# BSPD_Simulation.net
KiCad netlist of a schematic drawn in Altium Designer
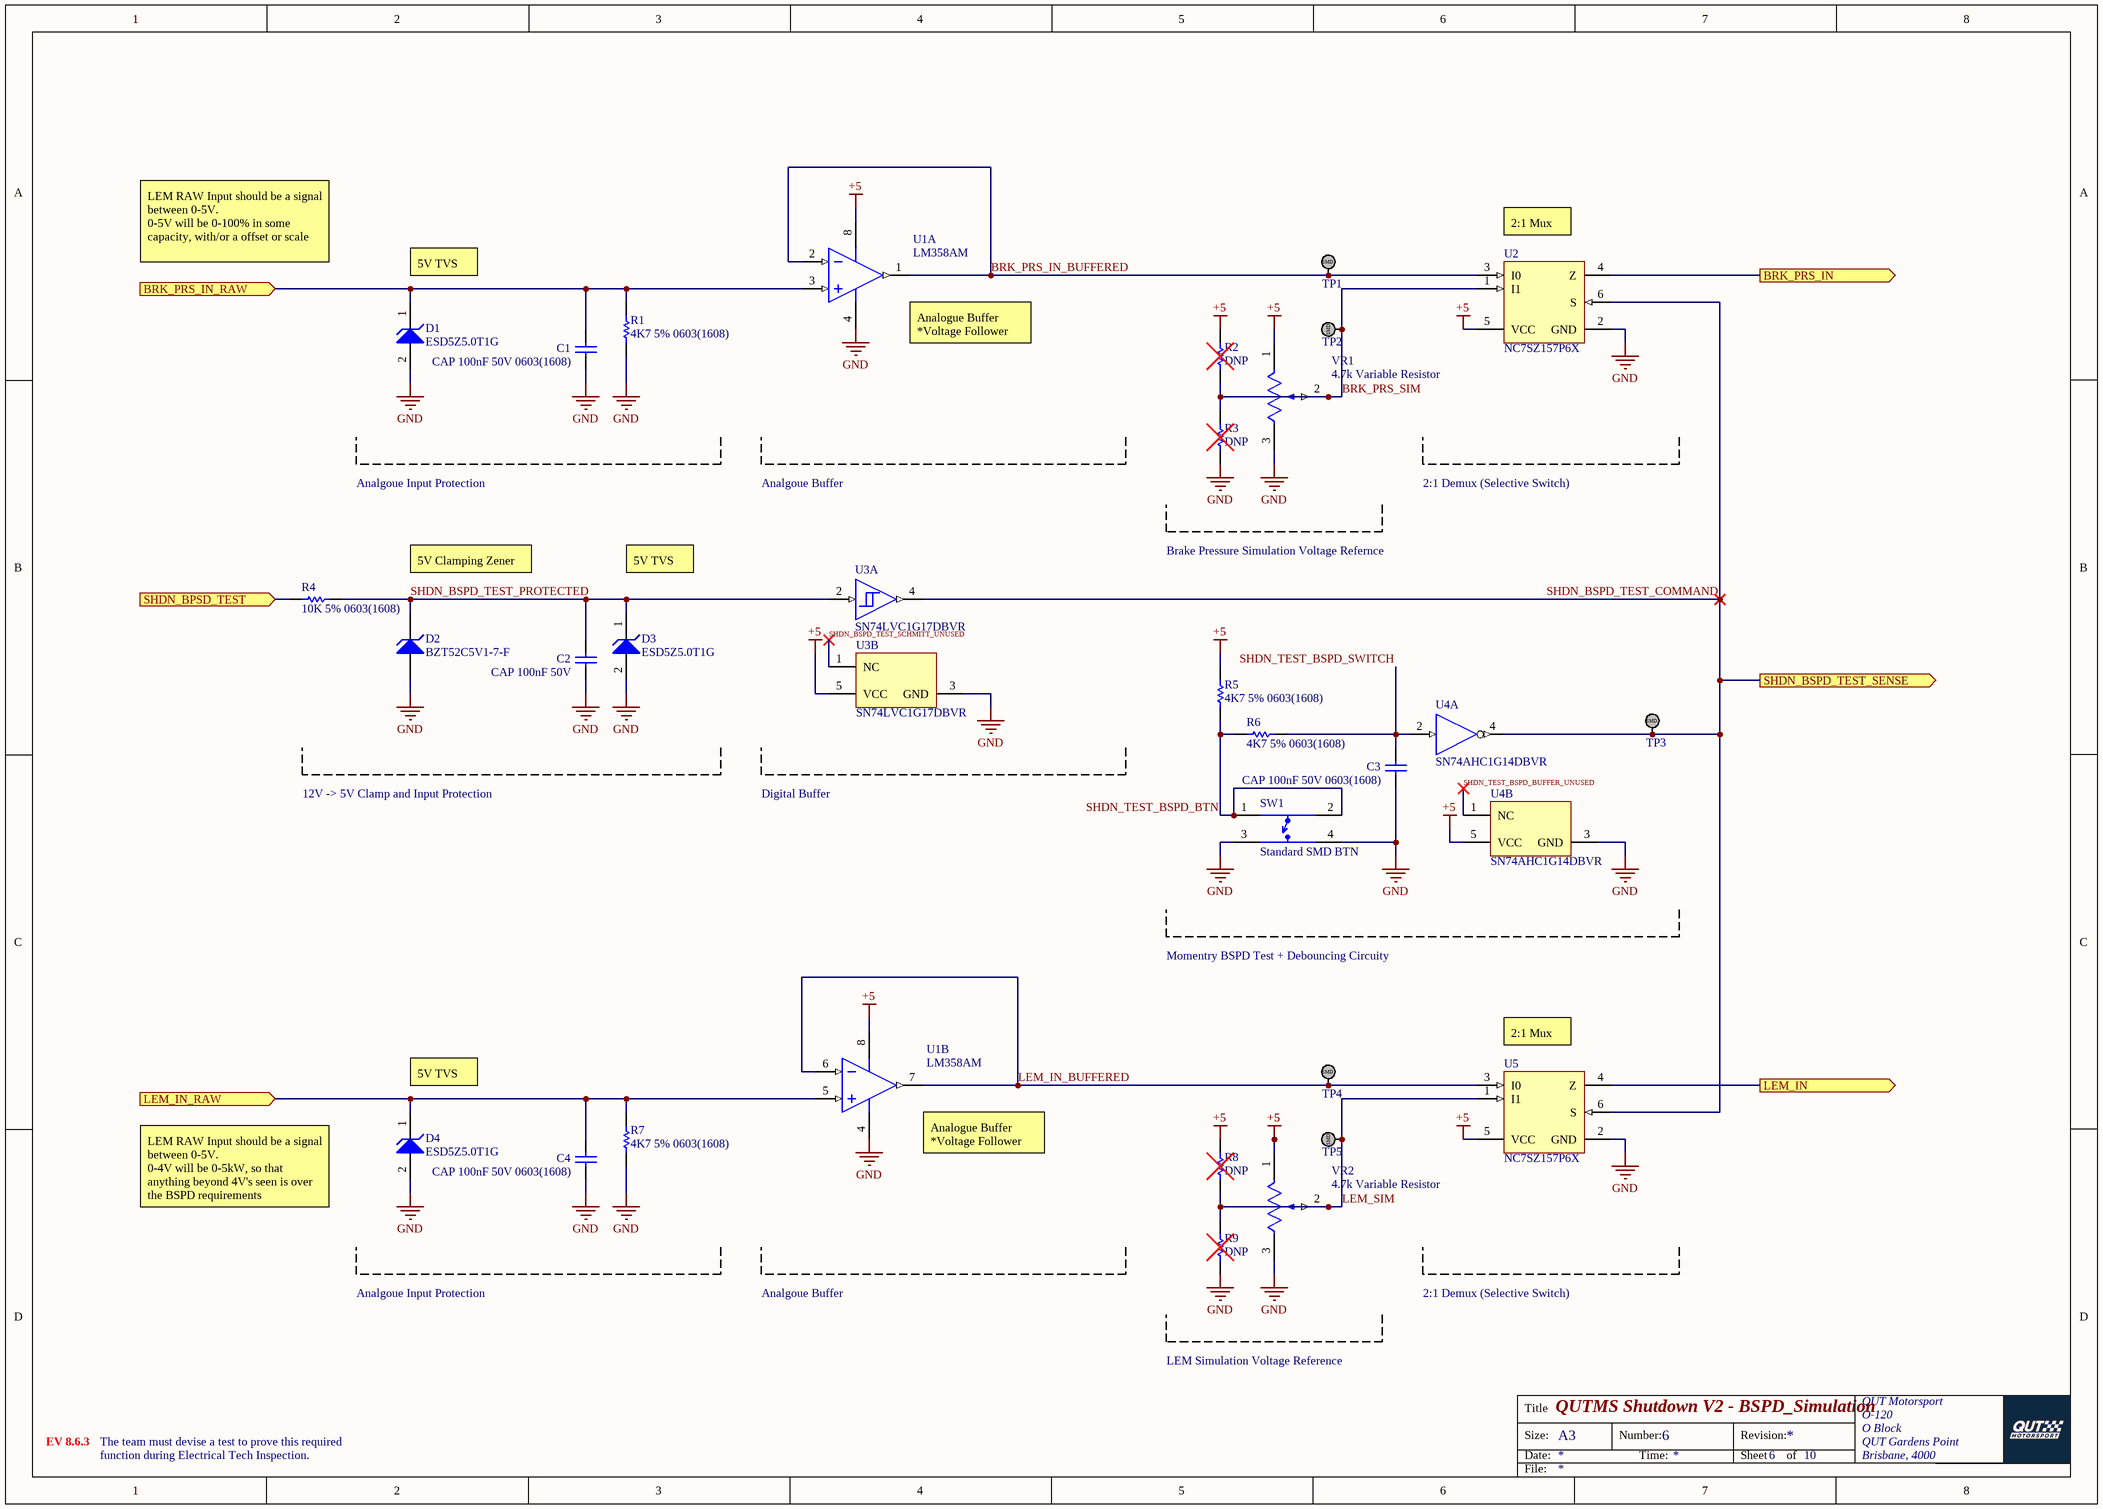
[diagram p0: BSPD_Simulation.SchDoc]

(export (version "E")
  (design (tool "Eeschema 10.0.6"))
  (components
    (comp (ref "C1")
      (value "CAP 100nF 50V 0603(1608)")
      (footprint "CAPC0603(1608)100_L")
      (description "CAP 100nF 50V ±5% 0603 (1608 Metric) Thickness 1mm SMD")
      (fields (field (name "TOLERANCE") "Â±5%"))
      (libsource (lib "Altium Content Vault") (part "CAP"))
    )
    (comp (ref "C2")
      (value "CAP 100nF 50V")
      (footprint "CAPC0603(1608)100_L")
      (description "CAP 100nF 50V ±5% 0603 (1608 Metric) Thickness 1mm SMD")
      (fields (field (name "TOLERANCE") "Â±5%"))
      (libsource (lib "Altium Content Vault") (part "CAP"))
    )
    (comp (ref "C3")
      (value "CAP 100nF 50V 0603(1608)")
      (footprint "CAPC0603(1608)100_L")
      (description "CAP 100nF 50V ±5% 0603 (1608 Metric) Thickness 1mm SMD")
      (fields (field (name "TOLERANCE") "Â±5%"))
      (libsource (lib "Altium Content Vault") (part "CAP"))
    )
    (comp (ref "C4")
      (value "CAP 100nF 50V 0603(1608)")
      (footprint "CAPC0603(1608)100_L")
      (description "CAP 100nF 50V ±5% 0603 (1608 Metric) Thickness 1mm SMD")
      (fields (field (name "TOLERANCE") "Â±5%"))
      (libsource (lib "Altium Content Vault") (part "CAP"))
    )
    (comp (ref "D1")
      (value "ESD5Z5.0T1G")
      (footprint "ONSC-SOD-523-2-502-01_V")
      (fields (field (name "MANUFACTURER") "On Semiconductor"))
      (libsource (lib "Altium Content Vault") (part "ONSC-K1A2-2"))
    )
    (comp (ref "D2")
      (value "BZT52C5V1-7-F")
      (footprint "DIOD-SOD123_V")
      (description "Surface Mount Zener Diode, 5.1 V, -65 to 150 degC, 2-Pin SMD (SOD-123), RoHS, Tape and Reel")
      (fields (field (name "MANUFACTURER") "DiodesIncorporated"))
      (libsource (lib "Altium Content Vault") (part "DZEN-AK-2"))
    )
    (comp (ref "D3")
      (value "ESD5Z5.0T1G")
      (footprint "ONSC-SOD-523-2-502-01_V")
      (fields (field (name "MANUFACTURER") "On Semiconductor"))
      (libsource (lib "Altium Content Vault") (part "ONSC-K1A2-2"))
    )
    (comp (ref "D4")
      (value "ESD5Z5.0T1G")
      (footprint "ONSC-SOD-523-2-502-01_V")
      (fields (field (name "MANUFACTURER") "On Semiconductor"))
      (libsource (lib "Altium Content Vault") (part "ONSC-K1A2-2"))
    )
    (comp (ref "R1")
      (value "4K7 5% 0603(1608)")
      (footprint "RESC0603(1608)_N")
      (description "4K7 0.1W 5% 0603 (1608 Metric)  SMD")
      (fields (field (name "TOLERANCE") "5 %") (field (name "POWER") "0.1 W"))
      (libsource (lib "Altium Content Vault") (part "RES"))
    )
    (comp (ref "R2")
      (value "DNP")
      (footprint "RESC0603(1608)_L")
      (description "0603 (1608 Metric) Chip Resistor")
      (libsource (lib "Altium Content Vault") (part "RES_3"))
    )
    (comp (ref "R3")
      (value "DNP")
      (footprint "RESC0603(1608)_L")
      (description "0603 (1608 Metric) Chip Resistor")
      (libsource (lib "Altium Content Vault") (part "RES_3"))
    )
    (comp (ref "R4")
      (value "10K 5% 0603(1608)")
      (footprint "RESC0603(1608)_N")
      (description "10K 0.1W 5% 0603 (1608 Metric)  SMD")
      (fields (field (name "TOLERANCE") "5 %") (field (name "POWER") "0.1 W"))
      (libsource (lib "Altium Content Vault") (part "RES"))
    )
    (comp (ref "R5")
      (value "4K7 5% 0603(1608)")
      (footprint "RESC0603(1608)_N")
      (description "4K7 0.1W 5% 0603 (1608 Metric)  SMD")
      (fields (field (name "TOLERANCE") "5 %") (field (name "POWER") "0.1 W"))
      (libsource (lib "Altium Content Vault") (part "RES"))
    )
    (comp (ref "R6")
      (value "4K7 5% 0603(1608)")
      (footprint "RESC0603(1608)_N")
      (description "4K7 0.1W 5% 0603 (1608 Metric)  SMD")
      (fields (field (name "TOLERANCE") "5 %") (field (name "POWER") "0.1 W"))
      (libsource (lib "Altium Content Vault") (part "RES"))
    )
    (comp (ref "R7")
      (value "4K7 5% 0603(1608)")
      (footprint "RESC0603(1608)_N")
      (description "4K7 0.1W 5% 0603 (1608 Metric)  SMD")
      (fields (field (name "TOLERANCE") "5 %") (field (name "POWER") "0.1 W"))
      (libsource (lib "Altium Content Vault") (part "RES"))
    )
    (comp (ref "R8")
      (value "DNP")
      (footprint "RESC0603(1608)_L")
      (description "0603 (1608 Metric) Chip Resistor")
      (libsource (lib "Altium Content Vault") (part "RES_3"))
    )
    (comp (ref "R9")
      (value "DNP")
      (footprint "RESC0603(1608)_L")
      (description "0603 (1608 Metric) Chip Resistor")
      (libsource (lib "Altium Content Vault") (part "RES_3"))
    )
    (comp (ref "SW1")
      (value "Standard SMD BTN")
      (footprint "StandardSMDBTN")
      (description "Cost common SMD button, 4 Lead")
      (libsource (lib "QUTMS_SwitchLibrary") (part "Standard SMD BTN"))
    )
    (comp (ref "TP1")
      (value "TestPoint_SMD")
      (footprint "TestPointSMD")
      (libsource (lib "StandardTest") (part "TestPoint_SMD"))
    )
    (comp (ref "TP2")
      (value "TestPoint_SMD")
      (footprint "TestPointSMD")
      (libsource (lib "StandardTest") (part "TestPoint_SMD"))
    )
    (comp (ref "TP3")
      (value "TestPoint_SMD")
      (footprint "TestPointSMD")
      (libsource (lib "StandardTest") (part "TestPoint_SMD"))
    )
    (comp (ref "TP4")
      (value "TestPoint_SMD")
      (footprint "TestPointSMD")
      (libsource (lib "StandardTest") (part "TestPoint_SMD"))
    )
    (comp (ref "TP5")
      (value "TestPoint_SMD")
      (footprint "TestPointSMD")
      (libsource (lib "StandardTest") (part "TestPoint_SMD"))
    )
    (comp (ref "U1")
      (value "LM358AM")
      (footprint "D0008A_N")
      (description "Low Power Dual Operational Amplifier, 8-pin Narrow SOIC")
      (fields (field (name "MANUFACTURER") "Texas Instruments"))
      (libsource (lib "Altium Content Vault") (part "AMP-OPA-LM158-8"))
    )
    (comp (ref "U2")
      (value "NC7SZ157P6X")
      (footprint "FAIR-SC70-6_V")
      (fields (field (name "MANUFACTURER") "FairchildSemiconductor"))
      (libsource (lib "Altium Content Vault") (part "FAIR-NC7SZ157-SC70-6"))
    )
    (comp (ref "U3")
      (value "SN74LVC1G17DBVR")
      (footprint "DBV0005A_L")
      (description "Single Schmitt-Trigger Buffer, DBV0005A, LARGE T&R")
      (fields
        (field (name "MANUFACTURER") "Texas Instruments")
        (field (name "GENERIC PART NUMBER") "SN74LVC1G17")
      )
      (libsource (lib "Altium Content Vault") (part "TI-SN74XXX1XXX-XX-5-SCHMITT"))
    )
    (comp (ref "U4")
      (value "SN74AHC1G14DBVR")
      (footprint "DBV0005A_L")
      (fields (field (name "MANUFACTURER") "Texas Instruments"))
      (libsource (lib "Altium Content Vault") (part "TI-SN74XXX1XX4-XX-5"))
    )
    (comp (ref "U5")
      (value "NC7SZ157P6X")
      (footprint "FAIR-SC70-6_V")
      (fields (field (name "MANUFACTURER") "FairchildSemiconductor"))
      (libsource (lib "Altium Content Vault") (part "FAIR-NC7SZ157-SC70-6"))
    )
    (comp (ref "VR1")
      (value "4.7k Variable Resistor")
      (footprint "VG039NCHXTB472")
      (description "4k7 ±25% ±250 ppm/°C SMD Variable Resistors RoHS ¦ VG039NCHXTB472")
      (libsource (lib "QUTMS_PotentiometerLibrary") (part "4.7k Variable Resistor"))
    )
    (comp (ref "VR2")
      (value "4.7k Variable Resistor")
      (footprint "VG039NCHXTB472")
      (description "4k7 ±25% ±250 ppm/°C SMD Variable Resistors RoHS ¦ VG039NCHXTB472")
      (libsource (lib "QUTMS_PotentiometerLibrary") (part "4.7k Variable Resistor"))
    )
  )
  (nets
    (net (code "1") (name "+5") (class "Default")
      (node (ref "R2") (pin "2") (pinfunction "2_2") (pintype "passive"))
      (node (ref "R5") (pin "2") (pinfunction "2_2") (pintype "passive"))
      (node (ref "R8") (pin "2") (pinfunction "2_2") (pintype "passive"))
      (node (ref "U1") (pin "8") (pinfunction "V+_8") (pintype "power_in"))
      (node (ref "U2") (pin "5") (pinfunction "VCC_5") (pintype "power_in"))
      (node (ref "U3") (pin "5") (pinfunction "VCC_5") (pintype "power_in"))
      (node (ref "U4") (pin "5") (pinfunction "VCC_5") (pintype "power_in"))
      (node (ref "U5") (pin "5") (pinfunction "VCC_5") (pintype "power_in"))
      (node (ref "VR1") (pin "1") (pinfunction "48_1") (pintype "passive"))
      (node (ref "VR2") (pin "1") (pinfunction "48_1") (pintype "passive"))
    )
    (net (code "2") (name "/BRK_PRS_IN") (class "Default")
      (node (ref "U2") (pin "4") (pinfunction "Z_4") (pintype "tri_state"))
    )
    (net (code "3") (name "/BRK_PRS_IN_BUFFERED") (class "Default")
      (node (ref "TP1") (pin "1") (pinfunction "1_1") (pintype "passive"))
      (node (ref "U1") (pin "1") (pinfunction "OUTA_1") (pintype "output"))
      (node (ref "U1") (pin "2") (pinfunction "INA-_2") (pintype "input"))
      (node (ref "U2") (pin "3") (pinfunction "I0_3") (pintype "input"))
    )
    (net (code "4") (name "/BRK_PRS_IN_RAW") (class "Default")
      (node (ref "C1") (pin "1") (pinfunction "1_1") (pintype "passive"))
      (node (ref "D1") (pin "1") (pinfunction "K_1") (pintype "passive"))
      (node (ref "R1") (pin "2") (pinfunction "2_2") (pintype "passive"))
      (node (ref "U1") (pin "3") (pinfunction "INA+_3") (pintype "input"))
    )
    (net (code "5") (name "/BRK_PRS_SIM") (class "Default")
      (node (ref "R2") (pin "1") (pinfunction "1_1") (pintype "passive"))
      (node (ref "R3") (pin "2") (pinfunction "2_2") (pintype "passive"))
      (node (ref "TP2") (pin "1") (pinfunction "1_1") (pintype "passive"))
      (node (ref "U2") (pin "1") (pinfunction "I1_1") (pintype "input"))
      (node (ref "VR1") (pin "2") (pinfunction "50_2") (pintype "output"))
    )
    (net (code "6") (name "/LEM_IN") (class "Default")
      (node (ref "U5") (pin "4") (pinfunction "Z_4") (pintype "tri_state"))
    )
    (net (code "7") (name "/LEM_IN_BUFFERED") (class "Default")
      (node (ref "TP4") (pin "1") (pinfunction "1_1") (pintype "passive"))
      (node (ref "U1") (pin "6") (pinfunction "INB-_6") (pintype "input"))
      (node (ref "U1") (pin "7") (pinfunction "OUTB_7") (pintype "output"))
      (node (ref "U5") (pin "3") (pinfunction "I0_3") (pintype "input"))
    )
    (net (code "8") (name "/LEM_IN_RAW") (class "Default")
      (node (ref "C4") (pin "1") (pinfunction "1_1") (pintype "passive"))
      (node (ref "D4") (pin "1") (pinfunction "K_1") (pintype "passive"))
      (node (ref "R7") (pin "2") (pinfunction "2_2") (pintype "passive"))
      (node (ref "U1") (pin "5") (pinfunction "INB+_5") (pintype "input"))
    )
    (net (code "9") (name "/LEM_SIM") (class "Default")
      (node (ref "R8") (pin "1") (pinfunction "1_1") (pintype "passive"))
      (node (ref "R9") (pin "2") (pinfunction "2_2") (pintype "passive"))
      (node (ref "TP5") (pin "1") (pinfunction "1_1") (pintype "passive"))
      (node (ref "U5") (pin "1") (pinfunction "I1_1") (pintype "input"))
      (node (ref "VR2") (pin "2") (pinfunction "50_2") (pintype "output"))
    )
    (net (code "10") (name "/SHDN_BPSD_TEST") (class "Default")
      (node (ref "R4") (pin "2") (pinfunction "2_2") (pintype "passive"))
    )
    (net (code "11") (name "/SHDN_BSPD_TEST_COMMAND") (class "Default")
      (node (ref "TP3") (pin "1") (pinfunction "1_1") (pintype "passive"))
      (node (ref "U2") (pin "6") (pinfunction "S_6") (pintype "input"))
      (node (ref "U3") (pin "4") (pinfunction "Y_4") (pintype "output"))
      (node (ref "U4") (pin "4") (pinfunction "Y_4") (pintype "output"))
      (node (ref "U5") (pin "6") (pinfunction "S_6") (pintype "input"))
    )
    (net (code "12") (name "/SHDN_BSPD_TEST_PROTECTED") (class "Default")
      (node (ref "C2") (pin "1") (pinfunction "1_1") (pintype "passive"))
      (node (ref "D2") (pin "2") (pinfunction "K_2") (pintype "passive"))
      (node (ref "D3") (pin "1") (pinfunction "K_1") (pintype "passive"))
      (node (ref "R4") (pin "1") (pinfunction "1_1") (pintype "passive"))
      (node (ref "U3") (pin "2") (pinfunction "A_2") (pintype "input"))
    )
    (net (code "13") (name "/SHDN_BSPD_TEST_SCHMITT_UNUSED") (class "Default")
      (node (ref "U3") (pin "1") (pinfunction "NC_1") (pintype "passive+no_connect"))
    )
    (net (code "14") (name "/SHDN_TEST_BSPD_BTN") (class "Default")
      (node (ref "R5") (pin "1") (pinfunction "1_1") (pintype "passive"))
      (node (ref "R6") (pin "2") (pinfunction "2_2") (pintype "passive"))
      (node (ref "SW1") (pin "1") (pinfunction "1_1") (pintype "passive"))
      (node (ref "SW1") (pin "2") (pinfunction "2_2") (pintype "passive"))
    )
    (net (code "15") (name "/SHDN_TEST_BSPD_BUFFER_UNUSED") (class "Default")
      (node (ref "U4") (pin "1") (pinfunction "NC_1") (pintype "passive+no_connect"))
    )
    (net (code "16") (name "/SHDN_TEST_BSPD_SWITCH") (class "Default")
      (node (ref "C3") (pin "1") (pinfunction "1_1") (pintype "passive"))
      (node (ref "R6") (pin "1") (pinfunction "1_1") (pintype "passive"))
      (node (ref "U4") (pin "2") (pinfunction "A_2") (pintype "input"))
    )
    (net (code "17") (name "GND") (class "Default")
      (node (ref "C1") (pin "2") (pinfunction "2_2") (pintype "passive"))
      (node (ref "C2") (pin "2") (pinfunction "2_2") (pintype "passive"))
      (node (ref "C3") (pin "2") (pinfunction "2_2") (pintype "passive"))
      (node (ref "C4") (pin "2") (pinfunction "2_2") (pintype "passive"))
      (node (ref "D1") (pin "2") (pinfunction "A_2") (pintype "passive"))
      (node (ref "D2") (pin "1") (pinfunction "A_1") (pintype "passive"))
      (node (ref "D3") (pin "2") (pinfunction "A_2") (pintype "passive"))
      (node (ref "D4") (pin "2") (pinfunction "A_2") (pintype "passive"))
      (node (ref "R1") (pin "1") (pinfunction "1_1") (pintype "passive"))
      (node (ref "R3") (pin "1") (pinfunction "1_1") (pintype "passive"))
      (node (ref "R7") (pin "1") (pinfunction "1_1") (pintype "passive"))
      (node (ref "R9") (pin "1") (pinfunction "1_1") (pintype "passive"))
      (node (ref "SW1") (pin "3") (pinfunction "3_3") (pintype "passive"))
      (node (ref "SW1") (pin "4") (pinfunction "4_4") (pintype "passive"))
      (node (ref "U1") (pin "4") (pinfunction "GND_4") (pintype "power_in"))
      (node (ref "U2") (pin "2") (pinfunction "GND_2") (pintype "power_in"))
      (node (ref "U3") (pin "3") (pinfunction "GND_3") (pintype "power_in"))
      (node (ref "U4") (pin "3") (pinfunction "GND_3") (pintype "power_in"))
      (node (ref "U5") (pin "2") (pinfunction "GND_2") (pintype "power_in"))
      (node (ref "VR1") (pin "3") (pinfunction "49_3") (pintype "passive"))
      (node (ref "VR2") (pin "3") (pinfunction "49_3") (pintype "passive"))
    )
  )
)
